# baby_board.net
KiCad netlist of a schematic drawn in EAGLE
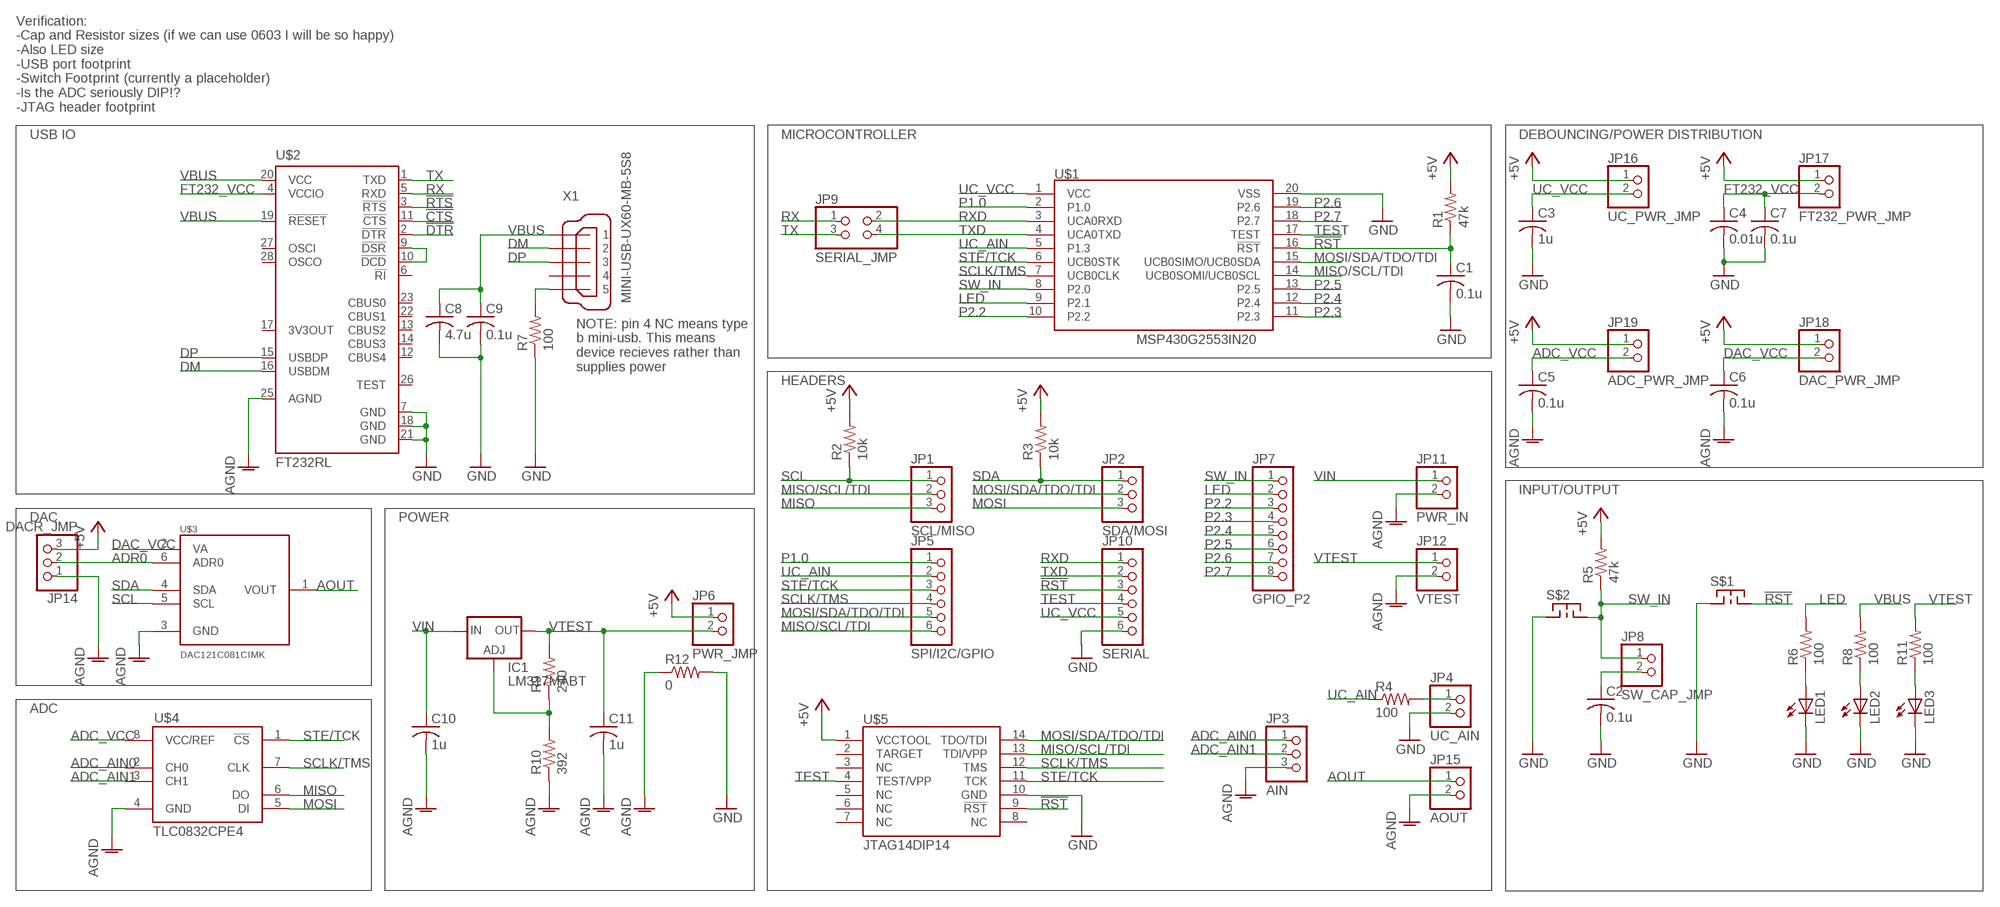
[diagram p0: schematic, sheet 1]

(export (version "E")
  (design (tool "Eeschema 10.0.6"))
  (components
    (comp (ref "C1")
      (value "0.1u")
      (footprint "eagle-import:C0603")
      (libsource (lib "eagle-import") (part "C-USC0603"))
    )
    (comp (ref "C2")
      (value "0.1u")
      (footprint "eagle-import:C0603")
      (libsource (lib "eagle-import") (part "C-USC0603"))
    )
    (comp (ref "C3")
      (value "1u")
      (footprint "eagle-import:C0603")
      (libsource (lib "eagle-import") (part "C-USC0603"))
    )
    (comp (ref "C4")
      (value "0.01u")
      (footprint "eagle-import:C0603")
      (libsource (lib "eagle-import") (part "C-USC0603"))
    )
    (comp (ref "C5")
      (value "0.1u")
      (footprint "eagle-import:C0603")
      (libsource (lib "eagle-import") (part "C-USC0603"))
    )
    (comp (ref "C6")
      (value "0.1u")
      (footprint "eagle-import:C0603")
      (libsource (lib "eagle-import") (part "C-USC0603"))
    )
    (comp (ref "C7")
      (value "0.1u")
      (footprint "eagle-import:C0603")
      (libsource (lib "eagle-import") (part "C-USC0603"))
    )
    (comp (ref "C8")
      (value "4.7u")
      (footprint "eagle-import:C0603")
      (libsource (lib "eagle-import") (part "C-USC0603"))
    )
    (comp (ref "C9")
      (value "0.1u")
      (footprint "eagle-import:C0603")
      (libsource (lib "eagle-import") (part "C-USC0603"))
    )
    (comp (ref "C10")
      (value "1u")
      (footprint "eagle-import:C0603")
      (libsource (lib "eagle-import") (part "C-USC0603"))
    )
    (comp (ref "C11")
      (value "1u")
      (footprint "eagle-import:C0603")
      (libsource (lib "eagle-import") (part "C-USC0603"))
    )
    (comp (ref "IC1")
      (value "LM317MABT")
      (footprint "eagle-import:TO220L1")
      (libsource (lib "eagle-import") (part "LM317?MABT"))
    )
    (comp (ref "JP1")
      (value "SCL/MISO")
      (footprint "eagle-import:1X03")
      (libsource (lib "eagle-import") (part "PINHD-1X3"))
    )
    (comp (ref "JP2")
      (value "SDA/MOSI")
      (footprint "eagle-import:1X03")
      (libsource (lib "eagle-import") (part "PINHD-1X3"))
    )
    (comp (ref "JP3")
      (value "AIN")
      (footprint "eagle-import:1X03")
      (libsource (lib "eagle-import") (part "PINHD-1X3"))
    )
    (comp (ref "JP4")
      (value "UC_AIN")
      (footprint "eagle-import:1X02")
      (libsource (lib "eagle-import") (part "PINHD-1X2"))
    )
    (comp (ref "JP5")
      (value "SPI/I2C/GPIO")
      (footprint "eagle-import:1X06")
      (libsource (lib "eagle-import") (part "PINHD-1X6"))
    )
    (comp (ref "JP6")
      (value "PWR_JMP")
      (footprint "eagle-import:1X02")
      (libsource (lib "eagle-import") (part "PINHD-1X2"))
    )
    (comp (ref "JP7")
      (value "GPIO_P2")
      (footprint "eagle-import:1X08")
      (libsource (lib "eagle-import") (part "PINHD-1X8"))
    )
    (comp (ref "JP8")
      (value "SW_CAP_JMP")
      (footprint "eagle-import:1X02")
      (libsource (lib "eagle-import") (part "PINHD-1X2"))
    )
    (comp (ref "JP9")
      (value "SERIAL_JMP")
      (footprint "eagle-import:2X02")
      (libsource (lib "eagle-import") (part "PINHD-2X2"))
    )
    (comp (ref "JP10")
      (value "SERIAL")
      (footprint "eagle-import:1X06")
      (libsource (lib "eagle-import") (part "PINHD-1X6"))
    )
    (comp (ref "JP11")
      (value "PWR_IN")
      (footprint "eagle-import:1X02")
      (libsource (lib "eagle-import") (part "PINHD-1X2"))
    )
    (comp (ref "JP12")
      (value "VTEST")
      (footprint "eagle-import:1X02")
      (libsource (lib "eagle-import") (part "PINHD-1X2"))
    )
    (comp (ref "JP14")
      (value "DACR_JMP")
      (footprint "eagle-import:1X03")
      (libsource (lib "eagle-import") (part "PINHD-1X3"))
    )
    (comp (ref "JP15")
      (value "AOUT")
      (footprint "eagle-import:1X02")
      (libsource (lib "eagle-import") (part "PINHD-1X2"))
    )
    (comp (ref "JP16")
      (value "UC_PWR_JMP")
      (footprint "eagle-import:1X02")
      (libsource (lib "eagle-import") (part "PINHD-1X2"))
    )
    (comp (ref "JP17")
      (value "FT232_PWR_JMP")
      (footprint "eagle-import:1X02")
      (libsource (lib "eagle-import") (part "PINHD-1X2"))
    )
    (comp (ref "JP18")
      (value "DAC_PWR_JMP")
      (footprint "eagle-import:1X02")
      (libsource (lib "eagle-import") (part "PINHD-1X2"))
    )
    (comp (ref "JP19")
      (value "ADC_PWR_JMP")
      (footprint "eagle-import:1X02")
      (libsource (lib "eagle-import") (part "PINHD-1X2"))
    )
    (comp (ref "LED1")
      (value "LEDCHIP-LED0805")
      (footprint "eagle-import:CHIP-LED0805")
      (libsource (lib "eagle-import") (part "LEDCHIP-LED0805"))
    )
    (comp (ref "LED2")
      (value "LEDCHIP-LED0805")
      (footprint "eagle-import:CHIP-LED0805")
      (libsource (lib "eagle-import") (part "LEDCHIP-LED0805"))
    )
    (comp (ref "LED3")
      (value "LEDCHIP-LED0805")
      (footprint "eagle-import:CHIP-LED0805")
      (libsource (lib "eagle-import") (part "LEDCHIP-LED0805"))
    )
    (comp (ref "R1")
      (value "47k")
      (footprint "eagle-import:R0603")
      (libsource (lib "eagle-import") (part "R-US_R0603"))
    )
    (comp (ref "R2")
      (value "10k")
      (footprint "eagle-import:R0603")
      (libsource (lib "eagle-import") (part "R-US_R0603"))
    )
    (comp (ref "R3")
      (value "10k")
      (footprint "eagle-import:R0603")
      (libsource (lib "eagle-import") (part "R-US_R0603"))
    )
    (comp (ref "R4")
      (value "100")
      (footprint "eagle-import:R0603")
      (libsource (lib "eagle-import") (part "R-US_R0603"))
    )
    (comp (ref "R5")
      (value "47k")
      (footprint "eagle-import:R0603")
      (libsource (lib "eagle-import") (part "R-US_R0603"))
    )
    (comp (ref "R6")
      (value "100")
      (footprint "eagle-import:R0603")
      (libsource (lib "eagle-import") (part "R-US_R0603"))
    )
    (comp (ref "R7")
      (value "100")
      (footprint "eagle-import:R0603")
      (libsource (lib "eagle-import") (part "R-US_R0603"))
    )
    (comp (ref "R8")
      (value "100")
      (footprint "eagle-import:R0603")
      (libsource (lib "eagle-import") (part "R-US_R0603"))
    )
    (comp (ref "R9")
      (value "240")
      (footprint "eagle-import:R0603")
      (libsource (lib "eagle-import") (part "R-US_R0603"))
    )
    (comp (ref "R10")
      (value "392")
      (footprint "eagle-import:R0603")
      (libsource (lib "eagle-import") (part "R-US_R0603"))
    )
    (comp (ref "R11")
      (value "100")
      (footprint "eagle-import:R0603")
      (libsource (lib "eagle-import") (part "R-US_R0603"))
    )
    (comp (ref "R12")
      (value "0")
      (footprint "eagle-import:R0603")
      (libsource (lib "eagle-import") (part "R-US_R0603"))
    )
    (comp (ref "S$1")
      (value "SWITCH_MOM_2_TEST")
      (footprint "eagle-import:TEST")
      (libsource (lib "eagle-import") (part "SWITCH_MOM_2_TEST"))
    )
    (comp (ref "S$2")
      (value "SWITCH_MOM_2_TEST")
      (footprint "eagle-import:TEST")
      (libsource (lib "eagle-import") (part "SWITCH_MOM_2_TEST"))
    )
    (comp (ref "U$1")
      (value "MSP430G2553IN20")
      (footprint "eagle-import:20-PDIP")
      (libsource (lib "eagle-import") (part "MSP430G2553IN20"))
    )
    (comp (ref "U$2")
      (value "FT232RL")
      (footprint "eagle-import:SSOP28")
      (libsource (lib "eagle-import") (part "FT232RL"))
    )
    (comp (ref "U$3")
      (value "DAC121C081CIMK")
      (footprint "eagle-import:SOT-6")
      (libsource (lib "eagle-import") (part "DAC121C081CIMK"))
    )
    (comp (ref "U$4")
      (value "TLC0832CPE4")
      (footprint "eagle-import:DIL08")
      (libsource (lib "eagle-import") (part "TLC0832CPE4"))
    )
    (comp (ref "U$5")
      (value "JTAG14DIP14")
      (footprint "eagle-import:DIL14")
      (libsource (lib "eagle-import") (part "JTAG14DIP14"))
    )
    (comp (ref "X1")
      (value "MINI-USB-UX60-MB-5S8")
      (footprint "eagle-import:UX60-MB-5S8")
      (libsource (lib "eagle-import") (part "MINI-USB-UX60-MB-5S8"))
    )
  )
  (nets
    (net (code "1") (name "+5V") (class "Default")
      (node (ref "JP14") (pin "3") (pinfunction "3_3") (pintype "passive"))
      (node (ref "JP16") (pin "1") (pinfunction "1_1") (pintype "passive"))
      (node (ref "JP17") (pin "1") (pinfunction "1_1") (pintype "passive"))
      (node (ref "JP18") (pin "1") (pinfunction "1_1") (pintype "passive"))
      (node (ref "JP19") (pin "1") (pinfunction "1_1") (pintype "passive"))
      (node (ref "JP6") (pin "1") (pinfunction "1_1") (pintype "passive"))
      (node (ref "R1") (pin "2") (pinfunction "2_2") (pintype "passive"))
      (node (ref "R2") (pin "2") (pinfunction "2_2") (pintype "passive"))
      (node (ref "R3") (pin "2") (pinfunction "2_2") (pintype "passive"))
      (node (ref "R5") (pin "2") (pinfunction "2_2") (pintype "passive"))
      (node (ref "U$5") (pin "1") (pinfunction "VCCTOOL_1") (pintype "bidirectional"))
    )
    (net (code "2") (name "/ADC_AIN0") (class "Default")
      (node (ref "JP3") (pin "1") (pinfunction "1_1") (pintype "passive"))
      (node (ref "U$4") (pin "2") (pinfunction "CH0_2") (pintype "input"))
    )
    (net (code "3") (name "/ADC_AIN1") (class "Default")
      (node (ref "JP3") (pin "2") (pinfunction "2_2") (pintype "passive"))
      (node (ref "U$4") (pin "3") (pinfunction "CH1_3") (pintype "input"))
    )
    (net (code "4") (name "/ADC_VCC") (class "Default")
      (node (ref "C5") (pin "1") (pinfunction "1_1") (pintype "passive"))
      (node (ref "JP19") (pin "2") (pinfunction "2_2") (pintype "passive"))
      (node (ref "U$4") (pin "8") (pinfunction "VCC/REF_8") (pintype "power_in"))
    )
    (net (code "5") (name "/ADR0") (class "Default")
      (node (ref "JP14") (pin "2") (pinfunction "2_2") (pintype "passive"))
      (node (ref "U$3") (pin "6") (pinfunction "ADR0_6") (pintype "input"))
    )
    (net (code "6") (name "/AOUT") (class "Default")
      (node (ref "JP15") (pin "1") (pinfunction "1_1") (pintype "passive"))
      (node (ref "U$3") (pin "1") (pinfunction "VOUT_1") (pintype "output"))
    )
    (net (code "7") (name "/DAC_VCC") (class "Default")
      (node (ref "C6") (pin "1") (pinfunction "1_1") (pintype "passive"))
      (node (ref "JP18") (pin "2") (pinfunction "2_2") (pintype "passive"))
      (node (ref "U$3") (pin "2") (pinfunction "VA_2") (pintype "power_in"))
    )
    (net (code "8") (name "/DM") (class "Default")
      (node (ref "U$2") (pin "16") (pinfunction "USBDM_16") (pintype "bidirectional"))
      (node (ref "X1") (pin "2") (pinfunction "2_2") (pintype "input"))
    )
    (net (code "9") (name "/DP") (class "Default")
      (node (ref "U$2") (pin "15") (pinfunction "USBDP_15") (pintype "bidirectional"))
      (node (ref "X1") (pin "3") (pinfunction "3_3") (pintype "input"))
    )
    (net (code "10") (name "/FT232_VCC") (class "Default")
      (node (ref "C4") (pin "1") (pinfunction "1_1") (pintype "passive"))
      (node (ref "C7") (pin "1") (pinfunction "1_1") (pintype "passive"))
      (node (ref "JP17") (pin "2") (pinfunction "2_2") (pintype "passive"))
      (node (ref "U$2") (pin "4") (pinfunction "VCCIO_4") (pintype "power_in"))
    )
    (net (code "11") (name "/LED") (class "Default")
      (node (ref "JP7") (pin "2") (pinfunction "2_2") (pintype "passive"))
      (node (ref "R6") (pin "2") (pinfunction "2_2") (pintype "passive"))
      (node (ref "U$1") (pin "9") (pinfunction "P2.1_9") (pintype "bidirectional"))
    )
    (net (code "12") (name "/MISO") (class "Default")
      (node (ref "JP1") (pin "3") (pinfunction "3_3") (pintype "passive"))
      (node (ref "U$4") (pin "6") (pinfunction "DO_6") (pintype "bidirectional"))
    )
    (net (code "13") (name "/MISO{slash}SCL{slash}TDI") (class "Default")
      (node (ref "JP1") (pin "2") (pinfunction "2_2") (pintype "passive"))
      (node (ref "JP5") (pin "6") (pinfunction "6_6") (pintype "passive"))
      (node (ref "U$1") (pin "14") (pinfunction "UCB0SOMI/UCB0SCL_14") (pintype "bidirectional"))
      (node (ref "U$5") (pin "13") (pinfunction "TDI/VPP_13") (pintype "bidirectional"))
    )
    (net (code "14") (name "/MOSI") (class "Default")
      (node (ref "JP2") (pin "3") (pinfunction "3_3") (pintype "passive"))
      (node (ref "U$4") (pin "5") (pinfunction "DI_5") (pintype "input"))
    )
    (net (code "15") (name "/MOSI{slash}SDA{slash}TDO{slash}TDI") (class "Default")
      (node (ref "JP2") (pin "2") (pinfunction "2_2") (pintype "passive"))
      (node (ref "JP5") (pin "5") (pinfunction "5_5") (pintype "passive"))
      (node (ref "U$1") (pin "15") (pinfunction "UCB0SIMO/UCB0SDA_15") (pintype "bidirectional"))
      (node (ref "U$5") (pin "14") (pinfunction "TDO/TDI_14") (pintype "bidirectional"))
    )
    (net (code "16") (name "/P1.0") (class "Default")
      (node (ref "JP5") (pin "1") (pinfunction "1_1") (pintype "passive"))
      (node (ref "U$1") (pin "2") (pinfunction "P1.0_2") (pintype "bidirectional"))
    )
    (net (code "17") (name "/P2.2") (class "Default")
      (node (ref "JP7") (pin "3") (pinfunction "3_3") (pintype "passive"))
      (node (ref "U$1") (pin "10") (pinfunction "P2.2_10") (pintype "bidirectional"))
    )
    (net (code "18") (name "/P2.3") (class "Default")
      (node (ref "JP7") (pin "4") (pinfunction "4_4") (pintype "passive"))
      (node (ref "U$1") (pin "11") (pinfunction "P2.3_11") (pintype "bidirectional"))
    )
    (net (code "19") (name "/P2.4") (class "Default")
      (node (ref "JP7") (pin "5") (pinfunction "5_5") (pintype "passive"))
      (node (ref "U$1") (pin "12") (pinfunction "P2.4_12") (pintype "bidirectional"))
    )
    (net (code "20") (name "/P2.5") (class "Default")
      (node (ref "JP7") (pin "6") (pinfunction "6_6") (pintype "passive"))
      (node (ref "U$1") (pin "13") (pinfunction "P2.5_13") (pintype "bidirectional"))
    )
    (net (code "21") (name "/P2.6") (class "Default")
      (node (ref "JP7") (pin "7") (pinfunction "7_7") (pintype "passive"))
      (node (ref "U$1") (pin "19") (pinfunction "P2.6_19") (pintype "bidirectional"))
    )
    (net (code "22") (name "/P2.7") (class "Default")
      (node (ref "JP7") (pin "8") (pinfunction "8_8") (pintype "passive"))
      (node (ref "U$1") (pin "18") (pinfunction "P2.7_18") (pintype "bidirectional"))
    )
    (net (code "23") (name "/RX") (class "Default")
      (node (ref "JP9") (pin "1") (pinfunction "1_1") (pintype "passive"))
      (node (ref "U$2") (pin "5") (pinfunction "RXD_5") (pintype "input"))
    )
    (net (code "24") (name "/RXD") (class "Default")
      (node (ref "JP10") (pin "1") (pinfunction "1_1") (pintype "passive"))
      (node (ref "JP9") (pin "2") (pinfunction "2_2") (pintype "passive"))
      (node (ref "U$1") (pin "3") (pinfunction "UCA0RXD_3") (pintype "bidirectional"))
    )
    (net (code "25") (name "/SCL") (class "Default")
      (node (ref "JP1") (pin "1") (pinfunction "1_1") (pintype "passive"))
      (node (ref "R2") (pin "1") (pinfunction "1_1") (pintype "passive"))
      (node (ref "U$3") (pin "5") (pinfunction "SCL_5") (pintype "input"))
    )
    (net (code "26") (name "/SCLK{slash}TMS") (class "Default")
      (node (ref "JP5") (pin "4") (pinfunction "4_4") (pintype "passive"))
      (node (ref "U$1") (pin "7") (pinfunction "UCB0CLK_7") (pintype "bidirectional"))
      (node (ref "U$4") (pin "7") (pinfunction "CLK_7") (pintype "input"))
      (node (ref "U$5") (pin "12") (pinfunction "TMS_12") (pintype "bidirectional"))
    )
    (net (code "27") (name "/SDA") (class "Default")
      (node (ref "JP2") (pin "1") (pinfunction "1_1") (pintype "passive"))
      (node (ref "R3") (pin "1") (pinfunction "1_1") (pintype "passive"))
      (node (ref "U$3") (pin "4") (pinfunction "SDA_4") (pintype "bidirectional"))
    )
    (net (code "28") (name "/STE{slash}TCK") (class "Default")
      (node (ref "JP5") (pin "3") (pinfunction "3_3") (pintype "passive"))
      (node (ref "U$1") (pin "6") (pinfunction "UCB0STK_6") (pintype "bidirectional"))
      (node (ref "U$4") (pin "1") (pinfunction "~{CS}_1") (pintype "input"))
      (node (ref "U$5") (pin "11") (pinfunction "TCK_11") (pintype "bidirectional"))
    )
    (net (code "29") (name "/SW_IN") (class "Default")
      (node (ref "JP7") (pin "1") (pinfunction "1_1") (pintype "passive"))
      (node (ref "JP8") (pin "1") (pinfunction "1_1") (pintype "passive"))
      (node (ref "R5") (pin "1") (pinfunction "1_1") (pintype "passive"))
      (node (ref "S$2") (pin "2") (pinfunction "2_2") (pintype "bidirectional"))
      (node (ref "U$1") (pin "8") (pinfunction "P2.0_8") (pintype "bidirectional"))
    )
    (net (code "30") (name "/TEST") (class "Default")
      (node (ref "JP10") (pin "4") (pinfunction "4_4") (pintype "passive"))
      (node (ref "U$1") (pin "17") (pinfunction "TEST_17") (pintype "bidirectional"))
      (node (ref "U$5") (pin "4") (pinfunction "TEST/VPP_4") (pintype "bidirectional"))
    )
    (net (code "31") (name "/TX") (class "Default")
      (node (ref "JP9") (pin "3") (pinfunction "3_3") (pintype "passive"))
      (node (ref "U$2") (pin "1") (pinfunction "TXD_1") (pintype "output"))
    )
    (net (code "32") (name "/TXD") (class "Default")
      (node (ref "JP10") (pin "2") (pinfunction "2_2") (pintype "passive"))
      (node (ref "JP9") (pin "4") (pinfunction "4_4") (pintype "passive"))
      (node (ref "U$1") (pin "4") (pinfunction "UCA0TXD_4") (pintype "bidirectional"))
    )
    (net (code "33") (name "/UC_AIN") (class "Default")
      (node (ref "JP5") (pin "2") (pinfunction "2_2") (pintype "passive"))
      (node (ref "R4") (pin "1") (pinfunction "1_1") (pintype "passive"))
      (node (ref "U$1") (pin "5") (pinfunction "P1.3_5") (pintype "bidirectional"))
    )
    (net (code "34") (name "/UC_VCC") (class "Default")
      (node (ref "C3") (pin "1") (pinfunction "1_1") (pintype "passive"))
      (node (ref "JP10") (pin "5") (pinfunction "5_5") (pintype "passive"))
      (node (ref "JP16") (pin "2") (pinfunction "2_2") (pintype "passive"))
      (node (ref "U$1") (pin "1") (pinfunction "VCC_1") (pintype "bidirectional"))
    )
    (net (code "35") (name "/VBUS") (class "Default")
      (node (ref "C8") (pin "1") (pinfunction "1_1") (pintype "passive"))
      (node (ref "C9") (pin "1") (pinfunction "1_1") (pintype "passive"))
      (node (ref "R8") (pin "2") (pinfunction "2_2") (pintype "passive"))
      (node (ref "U$2") (pin "19") (pinfunction "~{RESET}_19") (pintype "input"))
      (node (ref "U$2") (pin "20") (pinfunction "VCC_20") (pintype "power_in"))
      (node (ref "X1") (pin "1") (pinfunction "1_1") (pintype "input"))
    )
    (net (code "36") (name "/VIN") (class "Default")
      (node (ref "C10") (pin "1") (pinfunction "1_1") (pintype "passive"))
      (node (ref "IC1") (pin "3") (pinfunction "IN_3") (pintype "input"))
      (node (ref "JP11") (pin "1") (pinfunction "1_1") (pintype "passive"))
    )
    (net (code "37") (name "/VTEST") (class "Default")
      (node (ref "C11") (pin "1") (pinfunction "1_1") (pintype "passive"))
      (node (ref "IC1") (pin "2") (pinfunction "OUT_2") (pintype "passive"))
      (node (ref "JP12") (pin "1") (pinfunction "1_1") (pintype "passive"))
      (node (ref "JP6") (pin "2") (pinfunction "2_2") (pintype "passive"))
      (node (ref "R11") (pin "2") (pinfunction "2_2") (pintype "passive"))
      (node (ref "R9") (pin "2") (pinfunction "2_2") (pintype "passive"))
    )
    (net (code "38") (name "/~{CTS}") (class "Default")
      (node (ref "U$2") (pin "11") (pinfunction "~{CTS}_11") (pintype "input"))
    )
    (net (code "39") (name "/~{DTR}") (class "Default")
      (node (ref "U$2") (pin "2") (pinfunction "~{DTR}_2") (pintype "output"))
    )
    (net (code "40") (name "/~{RST}") (class "Default")
      (node (ref "C1") (pin "1") (pinfunction "1_1") (pintype "passive"))
      (node (ref "JP10") (pin "3") (pinfunction "3_3") (pintype "passive"))
      (node (ref "R1") (pin "1") (pinfunction "1_1") (pintype "passive"))
      (node (ref "S$1") (pin "2") (pinfunction "2_2") (pintype "bidirectional"))
      (node (ref "U$1") (pin "16") (pinfunction "~{RST}_16") (pintype "bidirectional"))
      (node (ref "U$5") (pin "9") (pinfunction "~{RST}_9") (pintype "bidirectional"))
    )
    (net (code "41") (name "/~{RTS}") (class "Default")
      (node (ref "U$2") (pin "3") (pinfunction "~{RTS}_3") (pintype "output"))
    )
    (net (code "42") (name "AGND") (class "Default")
      (node (ref "C10") (pin "2") (pinfunction "2_2") (pintype "passive"))
      (node (ref "C11") (pin "2") (pinfunction "2_2") (pintype "passive"))
      (node (ref "C5") (pin "2") (pinfunction "2_2") (pintype "passive"))
      (node (ref "C6") (pin "2") (pinfunction "2_2") (pintype "passive"))
      (node (ref "JP11") (pin "2") (pinfunction "2_2") (pintype "passive"))
      (node (ref "JP12") (pin "2") (pinfunction "2_2") (pintype "passive"))
      (node (ref "JP14") (pin "1") (pinfunction "1_1") (pintype "passive"))
      (node (ref "JP15") (pin "2") (pinfunction "2_2") (pintype "passive"))
      (node (ref "JP3") (pin "3") (pinfunction "3_3") (pintype "passive"))
      (node (ref "R10") (pin "1") (pinfunction "1_1") (pintype "passive"))
      (node (ref "R12") (pin "1") (pinfunction "1_1") (pintype "passive"))
      (node (ref "U$2") (pin "25") (pinfunction "AGND_25") (pintype "power_in"))
      (node (ref "U$3") (pin "3") (pinfunction "GND_3") (pintype "power_in"))
      (node (ref "U$4") (pin "4") (pinfunction "GND_4") (pintype "power_in"))
    )
    (net (code "43") (name "GND") (class "Default")
      (node (ref "C1") (pin "2") (pinfunction "2_2") (pintype "passive"))
      (node (ref "C2") (pin "2") (pinfunction "2_2") (pintype "passive"))
      (node (ref "C3") (pin "2") (pinfunction "2_2") (pintype "passive"))
      (node (ref "C4") (pin "2") (pinfunction "2_2") (pintype "passive"))
      (node (ref "C7") (pin "2") (pinfunction "2_2") (pintype "passive"))
      (node (ref "C8") (pin "2") (pinfunction "2_2") (pintype "passive"))
      (node (ref "C9") (pin "2") (pinfunction "2_2") (pintype "passive"))
      (node (ref "JP10") (pin "6") (pinfunction "6_6") (pintype "passive"))
      (node (ref "JP4") (pin "2") (pinfunction "2_2") (pintype "passive"))
      (node (ref "LED1") (pin "C") (pinfunction "C_C") (pintype "passive"))
      (node (ref "LED2") (pin "C") (pinfunction "C_C") (pintype "passive"))
      (node (ref "LED3") (pin "C") (pinfunction "C_C") (pintype "passive"))
      (node (ref "R12") (pin "2") (pinfunction "2_2") (pintype "passive"))
      (node (ref "R7") (pin "1") (pinfunction "1_1") (pintype "passive"))
      (node (ref "S$1") (pin "1") (pinfunction "1_1") (pintype "bidirectional"))
      (node (ref "S$2") (pin "1") (pinfunction "1_1") (pintype "bidirectional"))
      (node (ref "U$1") (pin "20") (pinfunction "VSS_20") (pintype "bidirectional"))
      (node (ref "U$2") (pin "18") (pinfunction "GND_18") (pintype "power_in"))
      (node (ref "U$2") (pin "21") (pinfunction "GND_21") (pintype "power_in"))
      (node (ref "U$2") (pin "7") (pinfunction "GND_7") (pintype "power_in"))
      (node (ref "U$5") (pin "10") (pinfunction "GND_10") (pintype "bidirectional"))
    )
    (net (code "44") (name "Net-(C2-Pad1)") (class "Default")
      (node (ref "C2") (pin "1") (pinfunction "1_1") (pintype "passive"))
      (node (ref "JP8") (pin "2") (pinfunction "2_2") (pintype "passive"))
    )
    (net (code "45") (name "Net-(IC1-ADJ)") (class "Default")
      (node (ref "IC1") (pin "1") (pinfunction "ADJ_1") (pintype "input"))
      (node (ref "R10") (pin "2") (pinfunction "2_2") (pintype "passive"))
      (node (ref "R9") (pin "1") (pinfunction "1_1") (pintype "passive"))
    )
    (net (code "46") (name "Net-(JP4-Pad1)") (class "Default")
      (node (ref "JP4") (pin "1") (pinfunction "1_1") (pintype "passive"))
      (node (ref "R4") (pin "2") (pinfunction "2_2") (pintype "passive"))
    )
    (net (code "47") (name "Net-(LED1-PadA)") (class "Default")
      (node (ref "LED1") (pin "A") (pinfunction "A_A") (pintype "passive"))
      (node (ref "R6") (pin "1") (pinfunction "1_1") (pintype "passive"))
    )
    (net (code "48") (name "Net-(LED2-PadA)") (class "Default")
      (node (ref "LED2") (pin "A") (pinfunction "A_A") (pintype "passive"))
      (node (ref "R8") (pin "1") (pinfunction "1_1") (pintype "passive"))
    )
    (net (code "49") (name "Net-(LED3-PadA)") (class "Default")
      (node (ref "LED3") (pin "A") (pinfunction "A_A") (pintype "passive"))
      (node (ref "R11") (pin "1") (pinfunction "1_1") (pintype "passive"))
    )
    (net (code "50") (name "Net-(R7-Pad2)") (class "Default")
      (node (ref "R7") (pin "2") (pinfunction "2_2") (pintype "passive"))
      (node (ref "X1") (pin "5") (pinfunction "5_5") (pintype "input"))
    )
    (net (code "51") (name "Net-(U$2-~{DCD})") (class "Default")
      (node (ref "U$2") (pin "10") (pinfunction "~{DCD}_10") (pintype "input"))
      (node (ref "U$2") (pin "9") (pinfunction "~{DSR}_9") (pintype "input"))
    )
    (net (code "52") (name "unconnected-(U$2-3V3OUT-Pad17)") (class "Default")
      (node (ref "U$2") (pin "17") (pinfunction "3V3OUT_17") (pintype "output"))
    )
    (net (code "53") (name "unconnected-(U$2-CBUS0-Pad23)") (class "Default")
      (node (ref "U$2") (pin "23") (pinfunction "CBUS0_23") (pintype "bidirectional"))
    )
    (net (code "54") (name "unconnected-(U$2-CBUS1-Pad22)") (class "Default")
      (node (ref "U$2") (pin "22") (pinfunction "CBUS1_22") (pintype "bidirectional"))
    )
    (net (code "55") (name "unconnected-(U$2-CBUS2-Pad13)") (class "Default")
      (node (ref "U$2") (pin "13") (pinfunction "CBUS2_13") (pintype "bidirectional"))
    )
    (net (code "56") (name "unconnected-(U$2-CBUS3-Pad14)") (class "Default")
      (node (ref "U$2") (pin "14") (pinfunction "CBUS3_14") (pintype "bidirectional"))
    )
    (net (code "57") (name "unconnected-(U$2-CBUS4-Pad12)") (class "Default")
      (node (ref "U$2") (pin "12") (pinfunction "CBUS4_12") (pintype "bidirectional"))
    )
    (net (code "58") (name "unconnected-(U$2-OSCI-Pad27)") (class "Default")
      (node (ref "U$2") (pin "27") (pinfunction "OSCI_27") (pintype "input"))
    )
    (net (code "59") (name "unconnected-(U$2-OSCO-Pad28)") (class "Default")
      (node (ref "U$2") (pin "28") (pinfunction "OSCO_28") (pintype "output"))
    )
    (net (code "60") (name "unconnected-(U$2-TEST-Pad26)") (class "Default")
      (node (ref "U$2") (pin "26") (pinfunction "TEST_26") (pintype "input"))
    )
    (net (code "61") (name "unconnected-(U$2-~{RI}-Pad6)") (class "Default")
      (node (ref "U$2") (pin "6") (pinfunction "~{RI}_6") (pintype "input"))
    )
    (net (code "62") (name "unconnected-(U$5-NC-Pad3)") (class "Default")
      (node (ref "U$5") (pin "3") (pinfunction "NC_3") (pintype "no_connect"))
    )
    (net (code "63") (name "unconnected-(U$5-NC-Pad5)") (class "Default")
      (node (ref "U$5") (pin "5") (pinfunction "NC_5") (pintype "no_connect"))
    )
    (net (code "64") (name "unconnected-(U$5-NC-Pad6)") (class "Default")
      (node (ref "U$5") (pin "6") (pinfunction "NC_6") (pintype "no_connect"))
    )
    (net (code "65") (name "unconnected-(U$5-NC-Pad7)") (class "Default")
      (node (ref "U$5") (pin "7") (pinfunction "NC_7") (pintype "no_connect"))
    )
    (net (code "66") (name "unconnected-(U$5-NC-Pad8)") (class "Default")
      (node (ref "U$5") (pin "8") (pinfunction "NC_8") (pintype "no_connect"))
    )
    (net (code "67") (name "unconnected-(U$5-TARGET-Pad2)") (class "Default")
      (node (ref "U$5") (pin "2") (pinfunction "TARGET_2") (pintype "bidirectional"))
    )
    (net (code "68") (name "unconnected-(X1-Pad4)") (class "Default")
      (node (ref "X1") (pin "4") (pinfunction "4_4") (pintype "input"))
    )
  )
)
